# nanobone.net
KiCad netlist of a schematic drawn in EAGLE
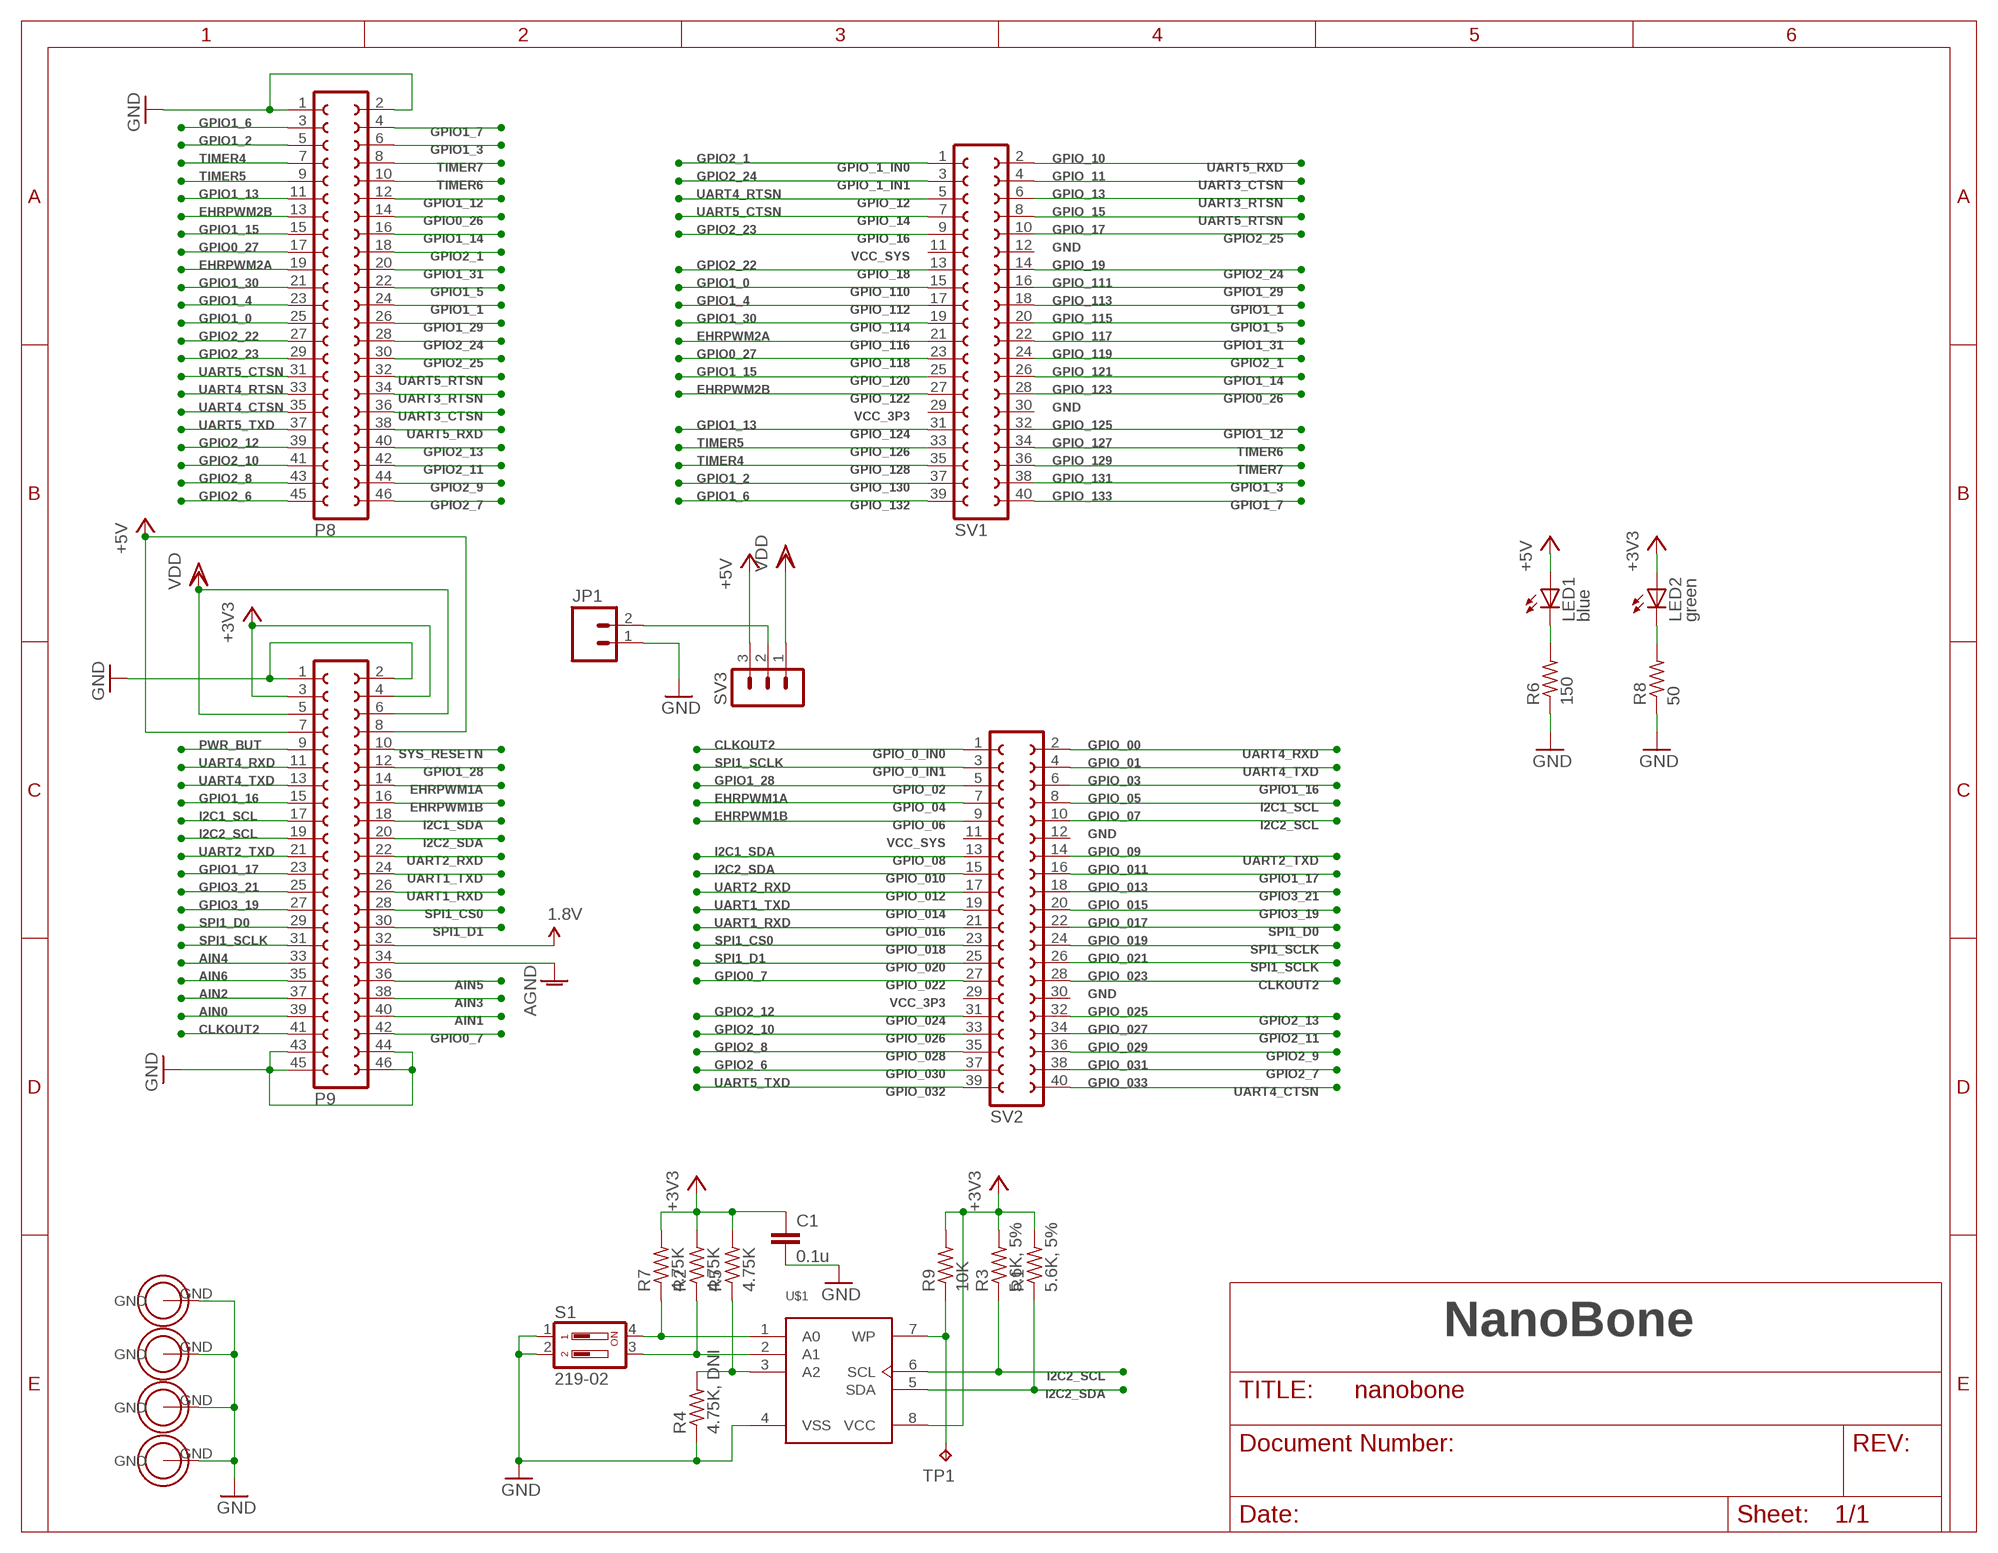
[diagram p0: schematic, sheet 1]

(export (version "E")
  (design (tool "Eeschema 10.0.6"))
  (components
    (comp (ref "C1")
      (value "0.1u")
      (footprint "eagle-import:C0603")
      (fields (field (name "MPN") "VJ0603V104ZXXCW1BC"))
      (libsource (lib "eagle-import") (part "C-EUC0603"))
    )
    (comp (ref "H1")
      (value "HOLE")
      (footprint "eagle-import:HOLE")
      (libsource (lib "eagle-import") (part "HOLE"))
    )
    (comp (ref "H2")
      (value "HOLE")
      (footprint "eagle-import:HOLE")
      (libsource (lib "eagle-import") (part "HOLE"))
    )
    (comp (ref "H3")
      (value "HOLE")
      (footprint "eagle-import:HOLE")
      (libsource (lib "eagle-import") (part "HOLE"))
    )
    (comp (ref "H4")
      (value "HOLE")
      (footprint "eagle-import:HOLE")
      (libsource (lib "eagle-import") (part "HOLE"))
    )
    (comp (ref "JP1")
      (value "M02LOCK_LONGPADS")
      (footprint "eagle-import:1X02_LOCK_LONGPADS")
      (libsource (lib "eagle-import") (part "M02LOCK_LONGPADS"))
    )
    (comp (ref "LED1")
      (value "blue")
      (footprint "eagle-import:CHIPLED_0603")
      (fields (field (name "MPN") "HT-193NB-5589"))
      (libsource (lib "eagle-import") (part "LEDCHIPLED_0603"))
    )
    (comp (ref "LED2")
      (value "green")
      (footprint "eagle-import:CHIPLED_0603")
      (fields (field (name "MPN") "LG Q971-KN-1"))
      (libsource (lib "eagle-import") (part "LEDCHIPLED_0603"))
    )
    (comp (ref "P8")
      (value "FE23-2_SMD")
      (footprint "eagle-import:FE23-2_SMD")
      (fields (field (name "MPN") "NPPC232KFMS-RC"))
      (libsource (lib "eagle-import") (part "FE23-2_SMD"))
    )
    (comp (ref "P9")
      (value "FE23-2_SMD")
      (footprint "eagle-import:FE23-2_SMD")
      (fields (field (name "MPN") "NPPC232KFMS-RC"))
      (libsource (lib "eagle-import") (part "FE23-2_SMD"))
    )
    (comp (ref "R1")
      (value "5.6K, 5%")
      (footprint "eagle-import:R0603")
      (fields (field (name "MPN") "RK73B1JTTDD562J"))
      (libsource (lib "eagle-import") (part "R-US_R0603"))
    )
    (comp (ref "R2")
      (value "4.75K")
      (footprint "eagle-import:R0603")
      (fields (field (name "MPN") "CR0603-FX-4751GLF"))
      (libsource (lib "eagle-import") (part "R-US_R0603"))
    )
    (comp (ref "R3")
      (value "5.6K, 5%")
      (footprint "eagle-import:R0603")
      (fields (field (name "MPN") "RK73B1JTTDD562J"))
      (libsource (lib "eagle-import") (part "R-US_R0603"))
    )
    (comp (ref "R4")
      (value "4.75K, DNI")
      (footprint "eagle-import:R0603")
      (fields (field (name "MPN") "CR0603-FX-4751GLF"))
      (libsource (lib "eagle-import") (part "R-US_R0603"))
    )
    (comp (ref "R5")
      (value "4.75K")
      (footprint "eagle-import:R0603")
      (fields (field (name "MPN") "CR0603-FX-4751GLF"))
      (libsource (lib "eagle-import") (part "R-US_R0603"))
    )
    (comp (ref "R6")
      (value "150")
      (footprint "eagle-import:R0603")
      (fields (field (name "MPN") "302-150-RC"))
      (libsource (lib "eagle-import") (part "R-US_R0603"))
    )
    (comp (ref "R7")
      (value "4.75K")
      (footprint "eagle-import:R0603")
      (fields (field (name "MPN") "CR0603-FX-4751GLF"))
      (libsource (lib "eagle-import") (part "R-US_R0603"))
    )
    (comp (ref "R8")
      (value "50")
      (footprint "eagle-import:R0603")
      (fields (field (name "MPN") "302-49.9-RC"))
      (libsource (lib "eagle-import") (part "R-US_R0603"))
    )
    (comp (ref "R9")
      (value "10K")
      (footprint "eagle-import:R0603")
      (fields (field (name "MPN") "WR06X1002FTL"))
      (libsource (lib "eagle-import") (part "R-US_R0603"))
    )
    (comp (ref "S1")
      (value "219-02")
      (footprint "eagle-import:CTS-219-02")
      (fields (field (name "MPN") "219-2MST"))
      (libsource (lib "eagle-import") (part "219-02"))
    )
    (comp (ref "SV1")
      (value "FE20-2")
      (footprint "eagle-import:FE20-2")
      (fields (field (name "MPN") "NPPC202KFMS-RC"))
      (libsource (lib "eagle-import") (part "FE20-2"))
    )
    (comp (ref "SV2")
      (value "FE20-2")
      (footprint "eagle-import:FE20-2")
      (fields (field (name "MPN") "NPPC202KFMS-RC"))
      (libsource (lib "eagle-import") (part "FE20-2"))
    )
    (comp (ref "SV3")
      (value "MA03-1")
      (footprint "eagle-import:MA03-1")
      (libsource (lib "eagle-import") (part "MA03-1"))
    )
    (comp (ref "TP1")
      (value "TPB2,54")
      (footprint "eagle-import:B2,54")
      (libsource (lib "eagle-import") (part "TPB2,54"))
    )
    (comp (ref "U$1")
      (value "CAT24C256")
      (footprint "eagle-import:SOIC8")
      (fields (field (name "MPN") "CAT24C256WI-GT3"))
      (libsource (lib "eagle-import") (part "CAT24C256"))
    )
  )
  (nets
    (net (code "1") (name "+3V3") (class "Default")
      (node (ref "C1") (pin "1") (pinfunction "1_1") (pintype "passive"))
      (node (ref "LED2") (pin "A") (pinfunction "A_A") (pintype "passive"))
      (node (ref "P9") (pin "3") (pinfunction "3_3") (pintype "passive"))
      (node (ref "P9") (pin "4") (pinfunction "4_4") (pintype "passive"))
      (node (ref "R1") (pin "2") (pinfunction "2_2") (pintype "passive"))
      (node (ref "R2") (pin "2") (pinfunction "2_2") (pintype "passive"))
      (node (ref "R3") (pin "2") (pinfunction "2_2") (pintype "passive"))
      (node (ref "R5") (pin "2") (pinfunction "2_2") (pintype "passive"))
      (node (ref "R7") (pin "2") (pinfunction "2_2") (pintype "passive"))
      (node (ref "R9") (pin "2") (pinfunction "2_2") (pintype "passive"))
      (node (ref "U$1") (pin "8") (pinfunction "VCC_8") (pintype "power_in"))
    )
    (net (code "2") (name "+5V") (class "Default")
      (node (ref "LED1") (pin "A") (pinfunction "A_A") (pintype "passive"))
      (node (ref "P9") (pin "7") (pinfunction "7_7") (pintype "passive"))
      (node (ref "P9") (pin "8") (pinfunction "8_8") (pintype "passive"))
      (node (ref "SV3") (pin "3") (pinfunction "3_3") (pintype "passive"))
    )
    (net (code "3") (name "/AIN0") (class "Default")
      (node (ref "P9") (pin "39") (pinfunction "39_39") (pintype "passive"))
    )
    (net (code "4") (name "/AIN1") (class "Default")
      (node (ref "P9") (pin "40") (pinfunction "40_40") (pintype "passive"))
    )
    (net (code "5") (name "/AIN2") (class "Default")
      (node (ref "P9") (pin "37") (pinfunction "37_37") (pintype "passive"))
    )
    (net (code "6") (name "/AIN3") (class "Default")
      (node (ref "P9") (pin "38") (pinfunction "38_38") (pintype "passive"))
    )
    (net (code "7") (name "/AIN4") (class "Default")
      (node (ref "P9") (pin "33") (pinfunction "33_33") (pintype "passive"))
    )
    (net (code "8") (name "/AIN5") (class "Default")
      (node (ref "P9") (pin "36") (pinfunction "36_36") (pintype "passive"))
    )
    (net (code "9") (name "/AIN6") (class "Default")
      (node (ref "P9") (pin "35") (pinfunction "35_35") (pintype "passive"))
    )
    (net (code "10") (name "/CLKOUT2") (class "Default")
      (node (ref "P9") (pin "41") (pinfunction "41_41") (pintype "passive"))
      (node (ref "SV2") (pin "1") (pinfunction "1_1") (pintype "passive"))
      (node (ref "SV2") (pin "28") (pinfunction "28_28") (pintype "passive"))
    )
    (net (code "11") (name "/EHRPWM1A") (class "Default")
      (node (ref "P9") (pin "14") (pinfunction "14_14") (pintype "passive"))
      (node (ref "SV2") (pin "7") (pinfunction "7_7") (pintype "passive"))
    )
    (net (code "12") (name "/EHRPWM1B") (class "Default")
      (node (ref "P9") (pin "16") (pinfunction "16_16") (pintype "passive"))
      (node (ref "SV2") (pin "9") (pinfunction "9_9") (pintype "passive"))
    )
    (net (code "13") (name "/EHRPWM2A") (class "Default")
      (node (ref "P8") (pin "19") (pinfunction "19_19") (pintype "passive"))
      (node (ref "SV1") (pin "21") (pinfunction "21_21") (pintype "passive"))
    )
    (net (code "14") (name "/EHRPWM2B") (class "Default")
      (node (ref "P8") (pin "13") (pinfunction "13_13") (pintype "passive"))
      (node (ref "SV1") (pin "27") (pinfunction "27_27") (pintype "passive"))
    )
    (net (code "15") (name "/GPIO0_7") (class "Default")
      (node (ref "P9") (pin "42") (pinfunction "42_42") (pintype "passive"))
      (node (ref "SV2") (pin "27") (pinfunction "27_27") (pintype "passive"))
    )
    (net (code "16") (name "/GPIO0_26") (class "Default")
      (node (ref "P8") (pin "14") (pinfunction "14_14") (pintype "passive"))
      (node (ref "SV1") (pin "28") (pinfunction "28_28") (pintype "passive"))
    )
    (net (code "17") (name "/GPIO0_27") (class "Default")
      (node (ref "P8") (pin "17") (pinfunction "17_17") (pintype "passive"))
      (node (ref "SV1") (pin "23") (pinfunction "23_23") (pintype "passive"))
    )
    (net (code "18") (name "/GPIO1_0") (class "Default")
      (node (ref "P8") (pin "25") (pinfunction "25_25") (pintype "passive"))
      (node (ref "SV1") (pin "15") (pinfunction "15_15") (pintype "passive"))
    )
    (net (code "19") (name "/GPIO1_1") (class "Default")
      (node (ref "P8") (pin "24") (pinfunction "24_24") (pintype "passive"))
      (node (ref "SV1") (pin "18") (pinfunction "18_18") (pintype "passive"))
    )
    (net (code "20") (name "/GPIO1_2") (class "Default")
      (node (ref "P8") (pin "5") (pinfunction "5_5") (pintype "passive"))
      (node (ref "SV1") (pin "37") (pinfunction "37_37") (pintype "passive"))
    )
    (net (code "21") (name "/GPIO1_3") (class "Default")
      (node (ref "P8") (pin "6") (pinfunction "6_6") (pintype "passive"))
      (node (ref "SV1") (pin "38") (pinfunction "38_38") (pintype "passive"))
    )
    (net (code "22") (name "/GPIO1_4") (class "Default")
      (node (ref "P8") (pin "23") (pinfunction "23_23") (pintype "passive"))
      (node (ref "SV1") (pin "17") (pinfunction "17_17") (pintype "passive"))
    )
    (net (code "23") (name "/GPIO1_5") (class "Default")
      (node (ref "P8") (pin "22") (pinfunction "22_22") (pintype "passive"))
      (node (ref "SV1") (pin "20") (pinfunction "20_20") (pintype "passive"))
    )
    (net (code "24") (name "/GPIO1_6") (class "Default")
      (node (ref "P8") (pin "3") (pinfunction "3_3") (pintype "passive"))
      (node (ref "SV1") (pin "39") (pinfunction "39_39") (pintype "passive"))
    )
    (net (code "25") (name "/GPIO1_7") (class "Default")
      (node (ref "P8") (pin "4") (pinfunction "4_4") (pintype "passive"))
      (node (ref "SV1") (pin "40") (pinfunction "40_40") (pintype "passive"))
    )
    (net (code "26") (name "/GPIO1_12") (class "Default")
      (node (ref "P8") (pin "12") (pinfunction "12_12") (pintype "passive"))
      (node (ref "SV1") (pin "32") (pinfunction "32_32") (pintype "passive"))
    )
    (net (code "27") (name "/GPIO1_13") (class "Default")
      (node (ref "P8") (pin "11") (pinfunction "11_11") (pintype "passive"))
      (node (ref "SV1") (pin "31") (pinfunction "31_31") (pintype "passive"))
    )
    (net (code "28") (name "/GPIO1_14") (class "Default")
      (node (ref "P8") (pin "16") (pinfunction "16_16") (pintype "passive"))
      (node (ref "SV1") (pin "26") (pinfunction "26_26") (pintype "passive"))
    )
    (net (code "29") (name "/GPIO1_15") (class "Default")
      (node (ref "P8") (pin "15") (pinfunction "15_15") (pintype "passive"))
      (node (ref "SV1") (pin "25") (pinfunction "25_25") (pintype "passive"))
    )
    (net (code "30") (name "/GPIO1_16") (class "Default")
      (node (ref "P9") (pin "15") (pinfunction "15_15") (pintype "passive"))
      (node (ref "SV2") (pin "6") (pinfunction "6_6") (pintype "passive"))
    )
    (net (code "31") (name "/GPIO1_17") (class "Default")
      (node (ref "P9") (pin "23") (pinfunction "23_23") (pintype "passive"))
      (node (ref "SV2") (pin "16") (pinfunction "16_16") (pintype "passive"))
    )
    (net (code "32") (name "/GPIO1_28") (class "Default")
      (node (ref "P9") (pin "12") (pinfunction "12_12") (pintype "passive"))
      (node (ref "SV2") (pin "5") (pinfunction "5_5") (pintype "passive"))
    )
    (net (code "33") (name "/GPIO1_29") (class "Default")
      (node (ref "P8") (pin "26") (pinfunction "26_26") (pintype "passive"))
      (node (ref "SV1") (pin "16") (pinfunction "16_16") (pintype "passive"))
    )
    (net (code "34") (name "/GPIO1_30") (class "Default")
      (node (ref "P8") (pin "21") (pinfunction "21_21") (pintype "passive"))
      (node (ref "SV1") (pin "19") (pinfunction "19_19") (pintype "passive"))
    )
    (net (code "35") (name "/GPIO1_31") (class "Default")
      (node (ref "P8") (pin "20") (pinfunction "20_20") (pintype "passive"))
      (node (ref "SV1") (pin "22") (pinfunction "22_22") (pintype "passive"))
    )
    (net (code "36") (name "/GPIO2_1") (class "Default")
      (node (ref "P8") (pin "18") (pinfunction "18_18") (pintype "passive"))
      (node (ref "SV1") (pin "1") (pinfunction "1_1") (pintype "passive"))
      (node (ref "SV1") (pin "24") (pinfunction "24_24") (pintype "passive"))
    )
    (net (code "37") (name "/GPIO2_6") (class "Default")
      (node (ref "P8") (pin "45") (pinfunction "45_45") (pintype "passive"))
      (node (ref "SV2") (pin "37") (pinfunction "37_37") (pintype "passive"))
    )
    (net (code "38") (name "/GPIO2_7") (class "Default")
      (node (ref "P8") (pin "46") (pinfunction "46_46") (pintype "passive"))
      (node (ref "SV2") (pin "38") (pinfunction "38_38") (pintype "passive"))
    )
    (net (code "39") (name "/GPIO2_8") (class "Default")
      (node (ref "P8") (pin "43") (pinfunction "43_43") (pintype "passive"))
      (node (ref "SV2") (pin "35") (pinfunction "35_35") (pintype "passive"))
    )
    (net (code "40") (name "/GPIO2_9") (class "Default")
      (node (ref "P8") (pin "44") (pinfunction "44_44") (pintype "passive"))
      (node (ref "SV2") (pin "36") (pinfunction "36_36") (pintype "passive"))
    )
    (net (code "41") (name "/GPIO2_10") (class "Default")
      (node (ref "P8") (pin "41") (pinfunction "41_41") (pintype "passive"))
      (node (ref "SV2") (pin "33") (pinfunction "33_33") (pintype "passive"))
    )
    (net (code "42") (name "/GPIO2_11") (class "Default")
      (node (ref "P8") (pin "42") (pinfunction "42_42") (pintype "passive"))
      (node (ref "SV2") (pin "34") (pinfunction "34_34") (pintype "passive"))
    )
    (net (code "43") (name "/GPIO2_12") (class "Default")
      (node (ref "P8") (pin "39") (pinfunction "39_39") (pintype "passive"))
      (node (ref "SV2") (pin "31") (pinfunction "31_31") (pintype "passive"))
    )
    (net (code "44") (name "/GPIO2_13") (class "Default")
      (node (ref "P8") (pin "40") (pinfunction "40_40") (pintype "passive"))
      (node (ref "SV2") (pin "32") (pinfunction "32_32") (pintype "passive"))
    )
    (net (code "45") (name "/GPIO2_22") (class "Default")
      (node (ref "P8") (pin "27") (pinfunction "27_27") (pintype "passive"))
      (node (ref "SV1") (pin "13") (pinfunction "13_13") (pintype "passive"))
    )
    (net (code "46") (name "/GPIO2_23") (class "Default")
      (node (ref "P8") (pin "29") (pinfunction "29_29") (pintype "passive"))
      (node (ref "SV1") (pin "9") (pinfunction "9_9") (pintype "passive"))
    )
    (net (code "47") (name "/GPIO2_24") (class "Default")
      (node (ref "P8") (pin "28") (pinfunction "28_28") (pintype "passive"))
      (node (ref "SV1") (pin "14") (pinfunction "14_14") (pintype "passive"))
      (node (ref "SV1") (pin "3") (pinfunction "3_3") (pintype "passive"))
    )
    (net (code "48") (name "/GPIO2_25") (class "Default")
      (node (ref "P8") (pin "30") (pinfunction "30_30") (pintype "passive"))
      (node (ref "SV1") (pin "10") (pinfunction "10_10") (pintype "passive"))
    )
    (net (code "49") (name "/GPIO3_19") (class "Default")
      (node (ref "P9") (pin "27") (pinfunction "27_27") (pintype "passive"))
      (node (ref "SV2") (pin "20") (pinfunction "20_20") (pintype "passive"))
    )
    (net (code "50") (name "/GPIO3_21") (class "Default")
      (node (ref "P9") (pin "25") (pinfunction "25_25") (pintype "passive"))
      (node (ref "SV2") (pin "18") (pinfunction "18_18") (pintype "passive"))
    )
    (net (code "51") (name "/I2C1_SCL") (class "Default")
      (node (ref "P9") (pin "17") (pinfunction "17_17") (pintype "passive"))
      (node (ref "SV2") (pin "8") (pinfunction "8_8") (pintype "passive"))
    )
    (net (code "52") (name "/I2C1_SDA") (class "Default")
      (node (ref "P9") (pin "18") (pinfunction "18_18") (pintype "passive"))
      (node (ref "SV2") (pin "13") (pinfunction "13_13") (pintype "passive"))
    )
    (net (code "53") (name "/I2C2_SCL") (class "Default")
      (node (ref "P9") (pin "19") (pinfunction "19_19") (pintype "passive"))
      (node (ref "R3") (pin "1") (pinfunction "1_1") (pintype "passive"))
      (node (ref "SV2") (pin "10") (pinfunction "10_10") (pintype "passive"))
      (node (ref "U$1") (pin "6") (pinfunction "SCL_6") (pintype "open_collector"))
    )
    (net (code "54") (name "/I2C2_SDA") (class "Default")
      (node (ref "P9") (pin "20") (pinfunction "20_20") (pintype "passive"))
      (node (ref "R1") (pin "1") (pinfunction "1_1") (pintype "passive"))
      (node (ref "SV2") (pin "15") (pinfunction "15_15") (pintype "passive"))
      (node (ref "U$1") (pin "5") (pinfunction "SDA_5") (pintype "open_collector"))
    )
    (net (code "55") (name "/PWR_BUT") (class "Default")
      (node (ref "P9") (pin "9") (pinfunction "9_9") (pintype "passive"))
    )
    (net (code "56") (name "/SPI1_CS0") (class "Default")
      (node (ref "P9") (pin "28") (pinfunction "28_28") (pintype "passive"))
      (node (ref "SV2") (pin "23") (pinfunction "23_23") (pintype "passive"))
    )
    (net (code "57") (name "/SPI1_D0") (class "Default")
      (node (ref "P9") (pin "29") (pinfunction "29_29") (pintype "passive"))
      (node (ref "SV2") (pin "22") (pinfunction "22_22") (pintype "passive"))
    )
    (net (code "58") (name "/SPI1_D1") (class "Default")
      (node (ref "P9") (pin "30") (pinfunction "30_30") (pintype "passive"))
      (node (ref "SV2") (pin "25") (pinfunction "25_25") (pintype "passive"))
    )
    (net (code "59") (name "/SPI1_SCLK") (class "Default")
      (node (ref "P9") (pin "31") (pinfunction "31_31") (pintype "passive"))
      (node (ref "SV2") (pin "24") (pinfunction "24_24") (pintype "passive"))
      (node (ref "SV2") (pin "26") (pinfunction "26_26") (pintype "passive"))
      (node (ref "SV2") (pin "3") (pinfunction "3_3") (pintype "passive"))
    )
    (net (code "60") (name "/SYS_RESETN") (class "Default")
      (node (ref "P9") (pin "10") (pinfunction "10_10") (pintype "passive"))
    )
    (net (code "61") (name "/TIMER4") (class "Default")
      (node (ref "P8") (pin "7") (pinfunction "7_7") (pintype "passive"))
      (node (ref "SV1") (pin "35") (pinfunction "35_35") (pintype "passive"))
    )
    (net (code "62") (name "/TIMER5") (class "Default")
      (node (ref "P8") (pin "9") (pinfunction "9_9") (pintype "passive"))
      (node (ref "SV1") (pin "33") (pinfunction "33_33") (pintype "passive"))
    )
    (net (code "63") (name "/TIMER6") (class "Default")
      (node (ref "P8") (pin "10") (pinfunction "10_10") (pintype "passive"))
      (node (ref "SV1") (pin "34") (pinfunction "34_34") (pintype "passive"))
    )
    (net (code "64") (name "/TIMER7") (class "Default")
      (node (ref "P8") (pin "8") (pinfunction "8_8") (pintype "passive"))
      (node (ref "SV1") (pin "36") (pinfunction "36_36") (pintype "passive"))
    )
    (net (code "65") (name "/UART1_RXD") (class "Default")
      (node (ref "P9") (pin "26") (pinfunction "26_26") (pintype "passive"))
      (node (ref "SV2") (pin "21") (pinfunction "21_21") (pintype "passive"))
    )
    (net (code "66") (name "/UART1_TXD") (class "Default")
      (node (ref "P9") (pin "24") (pinfunction "24_24") (pintype "passive"))
      (node (ref "SV2") (pin "19") (pinfunction "19_19") (pintype "passive"))
    )
    (net (code "67") (name "/UART2_RXD") (class "Default")
      (node (ref "P9") (pin "22") (pinfunction "22_22") (pintype "passive"))
      (node (ref "SV2") (pin "17") (pinfunction "17_17") (pintype "passive"))
    )
    (net (code "68") (name "/UART2_TXD") (class "Default")
      (node (ref "P9") (pin "21") (pinfunction "21_21") (pintype "passive"))
      (node (ref "SV2") (pin "14") (pinfunction "14_14") (pintype "passive"))
    )
    (net (code "69") (name "/UART3_CTSN") (class "Default")
      (node (ref "P8") (pin "36") (pinfunction "36_36") (pintype "passive"))
      (node (ref "SV1") (pin "4") (pinfunction "4_4") (pintype "passive"))
    )
    (net (code "70") (name "/UART3_RTSN") (class "Default")
      (node (ref "P8") (pin "34") (pinfunction "34_34") (pintype "passive"))
      (node (ref "SV1") (pin "6") (pinfunction "6_6") (pintype "passive"))
    )
    (net (code "71") (name "/UART4_CTSN") (class "Default")
      (node (ref "P8") (pin "35") (pinfunction "35_35") (pintype "passive"))
      (node (ref "SV2") (pin "40") (pinfunction "40_40") (pintype "passive"))
    )
    (net (code "72") (name "/UART4_RTSN") (class "Default")
      (node (ref "P8") (pin "33") (pinfunction "33_33") (pintype "passive"))
      (node (ref "SV1") (pin "5") (pinfunction "5_5") (pintype "passive"))
    )
    (net (code "73") (name "/UART4_RXD") (class "Default")
      (node (ref "P9") (pin "11") (pinfunction "11_11") (pintype "passive"))
      (node (ref "SV2") (pin "2") (pinfunction "2_2") (pintype "passive"))
    )
    (net (code "74") (name "/UART4_TXD") (class "Default")
      (node (ref "P9") (pin "13") (pinfunction "13_13") (pintype "passive"))
      (node (ref "SV2") (pin "4") (pinfunction "4_4") (pintype "passive"))
    )
    (net (code "75") (name "/UART5_CTSN") (class "Default")
      (node (ref "P8") (pin "31") (pinfunction "31_31") (pintype "passive"))
      (node (ref "SV1") (pin "7") (pinfunction "7_7") (pintype "passive"))
    )
    (net (code "76") (name "/UART5_RTSN") (class "Default")
      (node (ref "P8") (pin "32") (pinfunction "32_32") (pintype "passive"))
      (node (ref "SV1") (pin "8") (pinfunction "8_8") (pintype "passive"))
    )
    (net (code "77") (name "/UART5_RXD") (class "Default")
      (node (ref "P8") (pin "38") (pinfunction "38_38") (pintype "passive"))
      (node (ref "SV1") (pin "2") (pinfunction "2_2") (pintype "passive"))
    )
    (net (code "78") (name "/UART5_TXD") (class "Default")
      (node (ref "P8") (pin "37") (pinfunction "37_37") (pintype "passive"))
      (node (ref "SV2") (pin "39") (pinfunction "39_39") (pintype "passive"))
    )
    (net (code "79") (name "1.8V") (class "Default")
      (node (ref "P9") (pin "32") (pinfunction "32_32") (pintype "passive"))
    )
    (net (code "80") (name "AGND") (class "Default")
      (node (ref "P9") (pin "34") (pinfunction "34_34") (pintype "passive"))
    )
    (net (code "81") (name "GND") (class "Default")
      (node (ref "C1") (pin "2") (pinfunction "2_2") (pintype "passive"))
      (node (ref "H1") (pin "GND") (pinfunction "GND_GND") (pintype "passive"))
      (node (ref "H2") (pin "GND") (pinfunction "GND_GND") (pintype "passive"))
      (node (ref "H3") (pin "GND") (pinfunction "GND_GND") (pintype "passive"))
      (node (ref "H4") (pin "GND") (pinfunction "GND_GND") (pintype "passive"))
      (node (ref "JP1") (pin "1") (pinfunction "1_1") (pintype "passive"))
      (node (ref "P8") (pin "1") (pinfunction "1_1") (pintype "passive"))
      (node (ref "P8") (pin "2") (pinfunction "2_2") (pintype "passive"))
      (node (ref "P9") (pin "1") (pinfunction "1_1") (pintype "passive"))
      (node (ref "P9") (pin "2") (pinfunction "2_2") (pintype "passive"))
      (node (ref "P9") (pin "43") (pinfunction "43_43") (pintype "passive"))
      (node (ref "P9") (pin "44") (pinfunction "44_44") (pintype "passive"))
      (node (ref "P9") (pin "45") (pinfunction "45_45") (pintype "passive"))
      (node (ref "P9") (pin "46") (pinfunction "46_46") (pintype "passive"))
      (node (ref "R4") (pin "1") (pinfunction "1_1") (pintype "passive"))
      (node (ref "R6") (pin "1") (pinfunction "1_1") (pintype "passive"))
      (node (ref "R8") (pin "1") (pinfunction "1_1") (pintype "passive"))
      (node (ref "S1") (pin "1") (pinfunction "1_1") (pintype "passive"))
      (node (ref "S1") (pin "2") (pinfunction "2_2") (pintype "passive"))
      (node (ref "U$1") (pin "4") (pinfunction "VSS_4") (pintype "power_in"))
    )
    (net (code "82") (name "Net-(JP1-Pad2)") (class "Default")
      (node (ref "JP1") (pin "2") (pinfunction "2_2") (pintype "passive"))
      (node (ref "SV3") (pin "2") (pinfunction "2_2") (pintype "passive"))
    )
    (net (code "83") (name "Net-(LED1-PadC)") (class "Default")
      (node (ref "LED1") (pin "C") (pinfunction "C_C") (pintype "passive"))
      (node (ref "R6") (pin "2") (pinfunction "2_2") (pintype "passive"))
    )
    (net (code "84") (name "Net-(LED2-PadC)") (class "Default")
      (node (ref "LED2") (pin "C") (pinfunction "C_C") (pintype "passive"))
      (node (ref "R8") (pin "2") (pinfunction "2_2") (pintype "passive"))
    )
    (net (code "85") (name "Net-(U$1-A0)") (class "Default")
      (node (ref "R7") (pin "1") (pinfunction "1_1") (pintype "passive"))
      (node (ref "S1") (pin "4") (pinfunction "4_4") (pintype "passive"))
      (node (ref "U$1") (pin "1") (pinfunction "A0_1") (pintype "input"))
    )
    (net (code "86") (name "Net-(U$1-A1)") (class "Default")
      (node (ref "R2") (pin "1") (pinfunction "1_1") (pintype "passive"))
      (node (ref "S1") (pin "3") (pinfunction "3_3") (pintype "passive"))
      (node (ref "U$1") (pin "2") (pinfunction "A1_2") (pintype "input"))
    )
    (net (code "87") (name "Net-(U$1-A2)") (class "Default")
      (node (ref "R4") (pin "2") (pinfunction "2_2") (pintype "passive"))
      (node (ref "R5") (pin "1") (pinfunction "1_1") (pintype "passive"))
      (node (ref "U$1") (pin "3") (pinfunction "A2_3") (pintype "input"))
    )
    (net (code "88") (name "Net-(U$1-WP)") (class "Default")
      (node (ref "R9") (pin "1") (pinfunction "1_1") (pintype "passive"))
      (node (ref "TP1") (pin "TP") (pinfunction "TP_TP") (pintype "input"))
      (node (ref "U$1") (pin "7") (pinfunction "WP_7") (pintype "input"))
    )
    (net (code "89") (name "VDD") (class "Default")
      (node (ref "P9") (pin "5") (pinfunction "5_5") (pintype "passive"))
      (node (ref "P9") (pin "6") (pinfunction "6_6") (pintype "passive"))
      (node (ref "SV3") (pin "1") (pinfunction "1_1") (pintype "passive"))
    )
    (net (code "90") (name "unconnected-(SV1-Pad11)") (class "Default")
      (node (ref "SV1") (pin "11") (pinfunction "11_11") (pintype "passive"))
    )
    (net (code "91") (name "unconnected-(SV1-Pad12)") (class "Default")
      (node (ref "SV1") (pin "12") (pinfunction "12_12") (pintype "passive"))
    )
    (net (code "92") (name "unconnected-(SV1-Pad29)") (class "Default")
      (node (ref "SV1") (pin "29") (pinfunction "29_29") (pintype "passive"))
    )
    (net (code "93") (name "unconnected-(SV1-Pad30)") (class "Default")
      (node (ref "SV1") (pin "30") (pinfunction "30_30") (pintype "passive"))
    )
    (net (code "94") (name "unconnected-(SV2-Pad11)") (class "Default")
      (node (ref "SV2") (pin "11") (pinfunction "11_11") (pintype "passive"))
    )
    (net (code "95") (name "unconnected-(SV2-Pad12)") (class "Default")
      (node (ref "SV2") (pin "12") (pinfunction "12_12") (pintype "passive"))
    )
    (net (code "96") (name "unconnected-(SV2-Pad29)") (class "Default")
      (node (ref "SV2") (pin "29") (pinfunction "29_29") (pintype "passive"))
    )
    (net (code "97") (name "unconnected-(SV2-Pad30)") (class "Default")
      (node (ref "SV2") (pin "30") (pinfunction "30_30") (pintype "passive"))
    )
  )
)
